# amp_soha_v4.net
KiCad netlist of a schematic drawn in EAGLE
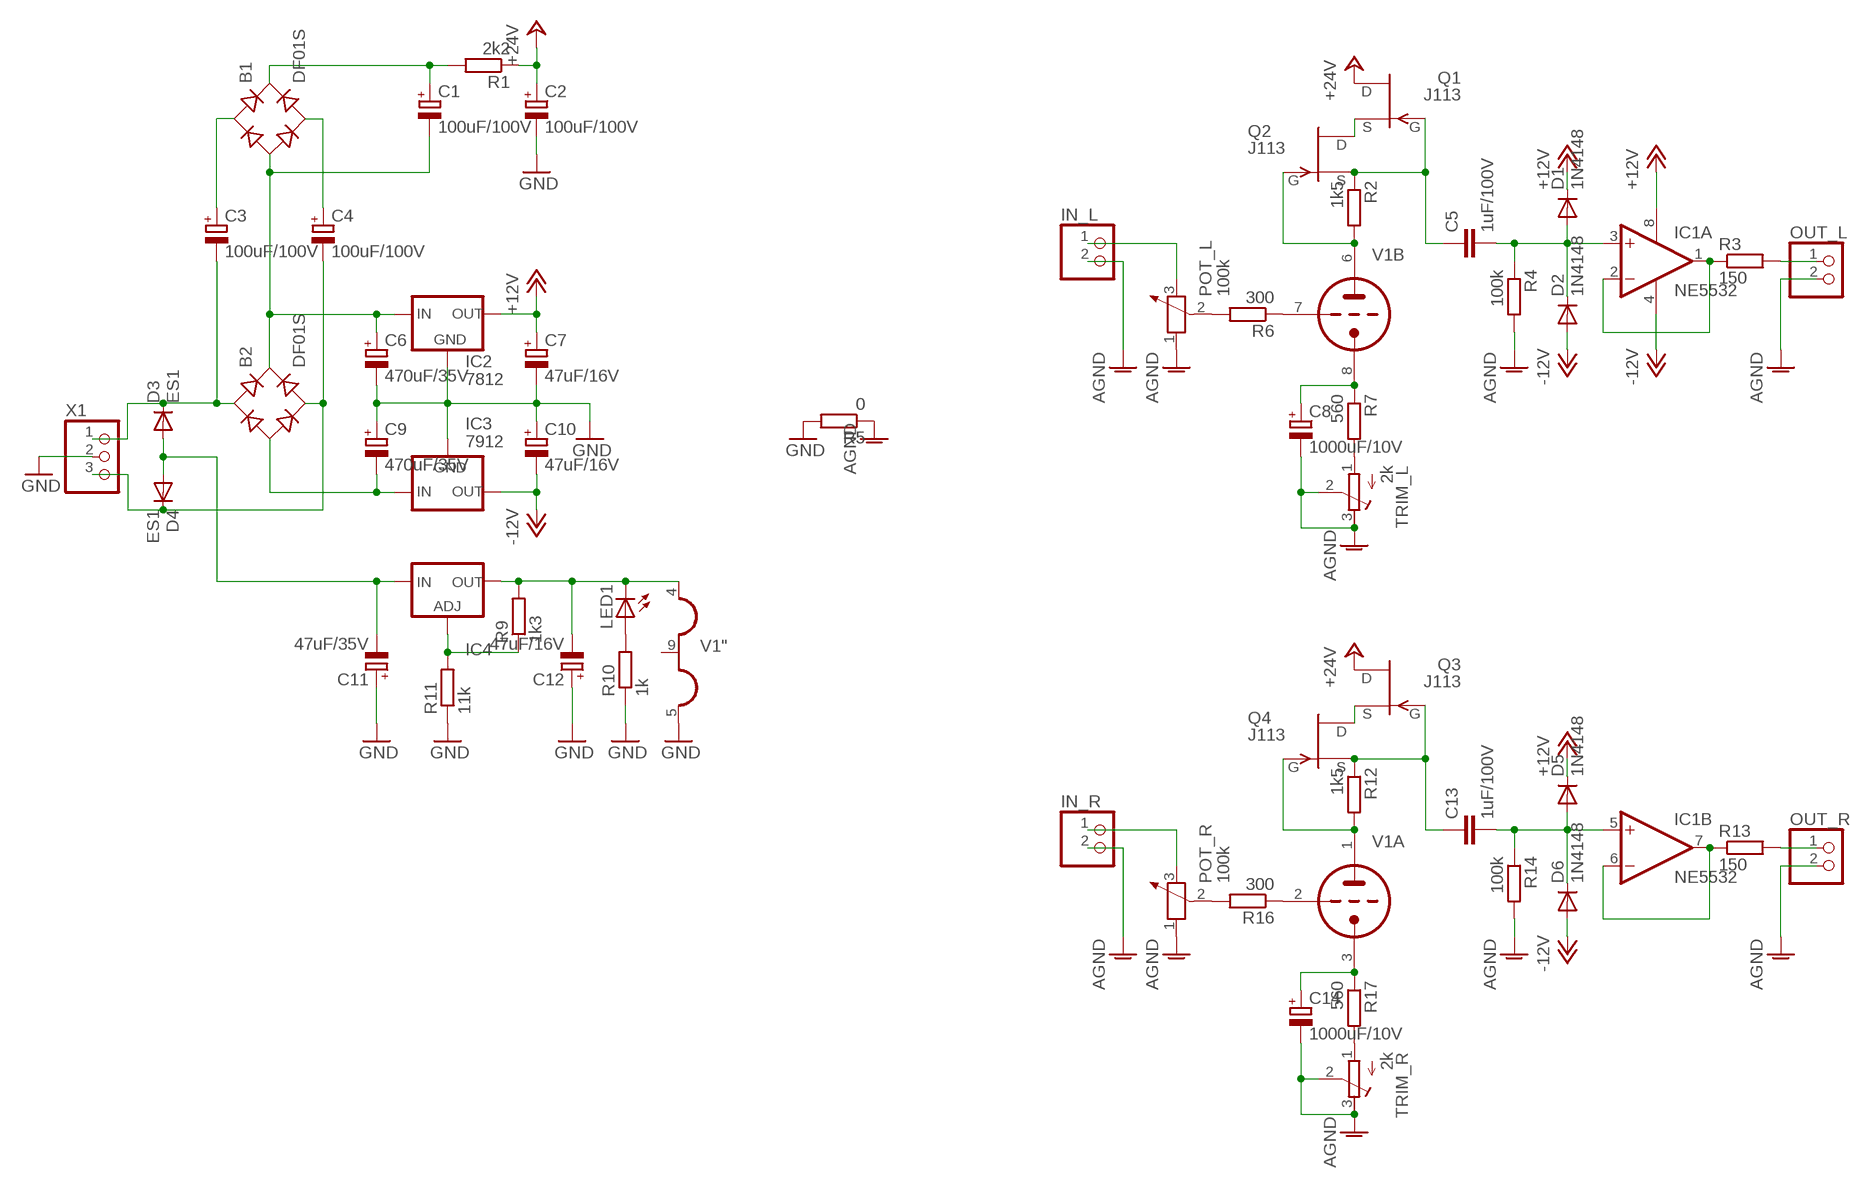
[diagram p0: schematic, sheet 1]

(export (version "E")
  (design (tool "Eeschema 10.0.6"))
  (components
    (comp (ref "B1")
      (value "DF01S")
      (footprint "eagle-import:DFS")
      (libsource (lib "eagle-import") (part "DFS01"))
    )
    (comp (ref "B2")
      (value "DF01S")
      (footprint "eagle-import:DFS")
      (libsource (lib "eagle-import") (part "DFS01"))
    )
    (comp (ref "C1")
      (value "100uF/100V")
      (footprint "eagle-import:E5-10,5")
      (libsource (lib "eagle-import") (part "CPOL-EUE5-10,5"))
    )
    (comp (ref "C2")
      (value "100uF/100V")
      (footprint "eagle-import:E5-10,5")
      (libsource (lib "eagle-import") (part "CPOL-EUE5-10,5"))
    )
    (comp (ref "C3")
      (value "100uF/100V")
      (footprint "eagle-import:E5-10,5")
      (libsource (lib "eagle-import") (part "CPOL-EUE5-10,5"))
    )
    (comp (ref "C4")
      (value "100uF/100V")
      (footprint "eagle-import:E5-10,5")
      (libsource (lib "eagle-import") (part "CPOL-EUE5-10,5"))
    )
    (comp (ref "C5")
      (value "1uF/100V")
      (footprint "eagle-import:C075-052X106")
      (libsource (lib "eagle-import") (part "C-EU075-052X106"))
    )
    (comp (ref "C6")
      (value "470uF/35V")
      (footprint "eagle-import:E5-10,5")
      (libsource (lib "eagle-import") (part "CPOL-EUE5-10,5"))
    )
    (comp (ref "C7")
      (value "47uF/16V")
      (footprint "eagle-import:E2,5-6")
      (libsource (lib "eagle-import") (part "CPOL-EUE2.5-6"))
    )
    (comp (ref "C8")
      (value "1000uF/10V")
      (footprint "eagle-import:E5-10,5")
      (libsource (lib "eagle-import") (part "CPOL-EUE5-10,5"))
    )
    (comp (ref "C9")
      (value "470uF/35V")
      (footprint "eagle-import:E5-10,5")
      (libsource (lib "eagle-import") (part "CPOL-EUE5-10,5"))
    )
    (comp (ref "C10")
      (value "47uF/16V")
      (footprint "eagle-import:E2,5-6")
      (libsource (lib "eagle-import") (part "CPOL-EUE2.5-6"))
    )
    (comp (ref "C11")
      (value "47uF/35V")
      (footprint "eagle-import:E2,5-6")
      (libsource (lib "eagle-import") (part "CPOL-EUE2.5-6"))
    )
    (comp (ref "C12")
      (value "47uF/16V")
      (footprint "eagle-import:E2,5-6")
      (libsource (lib "eagle-import") (part "CPOL-EUE2.5-6"))
    )
    (comp (ref "C13")
      (value "1uF/100V")
      (footprint "eagle-import:C075-052X106")
      (libsource (lib "eagle-import") (part "C-EU075-052X106"))
    )
    (comp (ref "C14")
      (value "1000uF/10V")
      (footprint "eagle-import:E5-10,5")
      (libsource (lib "eagle-import") (part "CPOL-EUE5-10,5"))
    )
    (comp (ref "D1")
      (value "1N4148")
      (footprint "eagle-import:D0805")
      (libsource (lib "eagle-import") (part "1N4148"))
    )
    (comp (ref "D2")
      (value "1N4148")
      (footprint "eagle-import:D0805")
      (libsource (lib "eagle-import") (part "1N4148"))
    )
    (comp (ref "D3")
      (value "ES1")
      (footprint "eagle-import:DO-214AC")
      (libsource (lib "eagle-import") (part "ES1"))
    )
    (comp (ref "D4")
      (value "ES1")
      (footprint "eagle-import:DO-214AC")
      (libsource (lib "eagle-import") (part "ES1"))
    )
    (comp (ref "D5")
      (value "1N4148")
      (footprint "eagle-import:D0805")
      (libsource (lib "eagle-import") (part "1N4148"))
    )
    (comp (ref "D6")
      (value "1N4148")
      (footprint "eagle-import:D0805")
      (libsource (lib "eagle-import") (part "1N4148"))
    )
    (comp (ref "IC1")
      (value "NE5532")
      (footprint "eagle-import:SO08")
      (libsource (lib "eagle-import") (part "NE5535U"))
    )
    (comp (ref "IC2")
      (value "7812")
      (footprint "eagle-import:78XXS")
      (libsource (lib "eagle-import") (part "78XXTO-220"))
    )
    (comp (ref "IC3")
      (value "7912")
      (footprint "eagle-import:79XXS")
      (libsource (lib "eagle-import") (part "79XXTO-220"))
    )
    (comp (ref "IC4")
      (value "LM337TS")
      (footprint "eagle-import:337TS")
      (libsource (lib "eagle-import") (part "LM337TS"))
    )
    (comp (ref "IN_L")
      (value "PINHD-1X2")
      (footprint "eagle-import:1X02")
      (libsource (lib "eagle-import") (part "PINHD-1X2"))
    )
    (comp (ref "IN_R")
      (value "PINHD-1X2")
      (footprint "eagle-import:1X02")
      (libsource (lib "eagle-import") (part "PINHD-1X2"))
    )
    (comp (ref "LED1")
      (value "LED5MM")
      (footprint "eagle-import:LED5MM")
      (libsource (lib "eagle-import") (part "LED5MM"))
    )
    (comp (ref "OUT_L")
      (value "PINHD-1X2")
      (footprint "eagle-import:1X02")
      (libsource (lib "eagle-import") (part "PINHD-1X2"))
    )
    (comp (ref "OUT_R")
      (value "PINHD-1X2")
      (footprint "eagle-import:1X02")
      (libsource (lib "eagle-import") (part "PINHD-1X2"))
    )
    (comp (ref "POT_L")
      (value "100k")
      (footprint "eagle-import:1X03")
      (libsource (lib "eagle-import") (part "POTENTIOMETER_"))
    )
    (comp (ref "POT_R")
      (value "100k")
      (footprint "eagle-import:1X03")
      (libsource (lib "eagle-import") (part "POTENTIOMETER_"))
    )
    (comp (ref "Q1")
      (value "J113")
      (footprint "eagle-import:TO92")
      (libsource (lib "eagle-import") (part "J113"))
    )
    (comp (ref "Q2")
      (value "J113")
      (footprint "eagle-import:TO92")
      (libsource (lib "eagle-import") (part "J113"))
    )
    (comp (ref "Q3")
      (value "J113")
      (footprint "eagle-import:TO92")
      (libsource (lib "eagle-import") (part "J113"))
    )
    (comp (ref "Q4")
      (value "J113")
      (footprint "eagle-import:TO92")
      (libsource (lib "eagle-import") (part "J113"))
    )
    (comp (ref "R1")
      (value "2k2")
      (footprint "eagle-import:R0805")
      (libsource (lib "eagle-import") (part "R-EU_"))
    )
    (comp (ref "R2")
      (value "1k5")
      (footprint "eagle-import:R0805")
      (libsource (lib "eagle-import") (part "R-EU_"))
    )
    (comp (ref "R3")
      (value "150")
      (footprint "eagle-import:R0805")
      (libsource (lib "eagle-import") (part "R-EU_"))
    )
    (comp (ref "R4")
      (value "100k")
      (footprint "eagle-import:R0805")
      (libsource (lib "eagle-import") (part "R-EU_"))
    )
    (comp (ref "R5")
      (value "0")
      (footprint "eagle-import:R0805")
      (libsource (lib "eagle-import") (part "R-EU_"))
    )
    (comp (ref "R6")
      (value "300")
      (footprint "eagle-import:R0805")
      (libsource (lib "eagle-import") (part "R-EU_"))
    )
    (comp (ref "R7")
      (value "560")
      (footprint "eagle-import:R0805")
      (libsource (lib "eagle-import") (part "R-EU_"))
    )
    (comp (ref "R9")
      (value "1k3")
      (footprint "eagle-import:R0805")
      (libsource (lib "eagle-import") (part "R-EU_"))
    )
    (comp (ref "R10")
      (value "1k")
      (footprint "eagle-import:R0805")
      (libsource (lib "eagle-import") (part "R-EU_"))
    )
    (comp (ref "R11")
      (value "11k")
      (footprint "eagle-import:R0805")
      (libsource (lib "eagle-import") (part "R-EU_"))
    )
    (comp (ref "R12")
      (value "1k5")
      (footprint "eagle-import:R0805")
      (libsource (lib "eagle-import") (part "R-EU_"))
    )
    (comp (ref "R13")
      (value "150")
      (footprint "eagle-import:R0805")
      (libsource (lib "eagle-import") (part "R-EU_"))
    )
    (comp (ref "R14")
      (value "100k")
      (footprint "eagle-import:R0805")
      (libsource (lib "eagle-import") (part "R-EU_"))
    )
    (comp (ref "R16")
      (value "300")
      (footprint "eagle-import:R0805")
      (libsource (lib "eagle-import") (part "R-EU_"))
    )
    (comp (ref "R17")
      (value "560")
      (footprint "eagle-import:R0805")
      (libsource (lib "eagle-import") (part "R-EU_"))
    )
    (comp (ref "TRIM_L")
      (value "2k")
      (footprint "eagle-import:RTRIM3296W")
      (libsource (lib "eagle-import") (part "RTRIM329W"))
    )
    (comp (ref "TRIM_R")
      (value "2k")
      (footprint "eagle-import:RTRIM3296W")
      (libsource (lib "eagle-import") (part "RTRIM329W"))
    )
    (comp (ref "V1")
      (value "12AU7-P")
      (footprint "eagle-import:NOVAL")
      (libsource (lib "eagle-import") (part "12AU7-P"))
    )
    (comp (ref "X1")
      (value "W237-103")
      (footprint "eagle-import:W237-103")
      (libsource (lib "eagle-import") (part "W237-103"))
    )
  )
  (nets
    (net (code "1") (name "+12V") (class "Default")
      (node (ref "C7") (pin "+") (pinfunction "+_+") (pintype "passive"))
      (node (ref "D1") (pin "K") (pinfunction "C_K") (pintype "passive"))
      (node (ref "D5") (pin "K") (pinfunction "C_K") (pintype "passive"))
      (node (ref "IC1") (pin "8") (pinfunction "V+_8") (pintype "power_in"))
      (node (ref "IC2") (pin "OUT") (pinfunction "OUT_OUT") (pintype "passive"))
    )
    (net (code "2") (name "+24V") (class "Default")
      (node (ref "C2") (pin "+") (pinfunction "+_+") (pintype "passive"))
      (node (ref "Q1") (pin "3") (pinfunction "D_3") (pintype "passive"))
      (node (ref "Q3") (pin "3") (pinfunction "D_3") (pintype "passive"))
      (node (ref "R1") (pin "1") (pinfunction "1_1") (pintype "passive"))
    )
    (net (code "3") (name "-12V") (class "Default")
      (node (ref "C10") (pin "-") (pinfunction "-_-") (pintype "passive"))
      (node (ref "D2") (pin "A") (pinfunction "A_A") (pintype "passive"))
      (node (ref "D6") (pin "A") (pinfunction "A_A") (pintype "passive"))
      (node (ref "IC1") (pin "4") (pinfunction "V-_4") (pintype "power_in"))
      (node (ref "IC3") (pin "OUT") (pinfunction "OUT_OUT") (pintype "passive"))
    )
    (net (code "4") (name "AGND") (class "Default")
      (node (ref "C14") (pin "-") (pinfunction "-_-") (pintype "passive"))
      (node (ref "C8") (pin "-") (pinfunction "-_-") (pintype "passive"))
      (node (ref "IN_L") (pin "2") (pinfunction "2_2") (pintype "passive"))
      (node (ref "IN_R") (pin "2") (pinfunction "2_2") (pintype "passive"))
      (node (ref "OUT_L") (pin "2") (pinfunction "2_2") (pintype "passive"))
      (node (ref "OUT_R") (pin "2") (pinfunction "2_2") (pintype "passive"))
      (node (ref "POT_L") (pin "1") (pinfunction "1_1") (pintype "passive"))
      (node (ref "POT_R") (pin "1") (pinfunction "1_1") (pintype "passive"))
      (node (ref "R14") (pin "2") (pinfunction "2_2") (pintype "passive"))
      (node (ref "R4") (pin "2") (pinfunction "2_2") (pintype "passive"))
      (node (ref "R5") (pin "1") (pinfunction "1_1") (pintype "passive"))
      (node (ref "TRIM_L") (pin "2") (pinfunction "S_2") (pintype "passive"))
      (node (ref "TRIM_L") (pin "3") (pinfunction "E_3") (pintype "passive"))
      (node (ref "TRIM_R") (pin "2") (pinfunction "S_2") (pintype "passive"))
      (node (ref "TRIM_R") (pin "3") (pinfunction "E_3") (pintype "passive"))
    )
    (net (code "5") (name "GND") (class "Default")
      (node (ref "C10") (pin "+") (pinfunction "+_+") (pintype "passive"))
      (node (ref "C11") (pin "+") (pinfunction "+_+") (pintype "passive"))
      (node (ref "C12") (pin "+") (pinfunction "+_+") (pintype "passive"))
      (node (ref "C2") (pin "-") (pinfunction "-_-") (pintype "passive"))
      (node (ref "C6") (pin "-") (pinfunction "-_-") (pintype "passive"))
      (node (ref "C7") (pin "-") (pinfunction "-_-") (pintype "passive"))
      (node (ref "C9") (pin "+") (pinfunction "+_+") (pintype "passive"))
      (node (ref "IC2") (pin "GND") (pinfunction "GND_GND") (pintype "input"))
      (node (ref "IC3") (pin "GND") (pinfunction "GND_GND") (pintype "input"))
      (node (ref "R10") (pin "1") (pinfunction "1_1") (pintype "passive"))
      (node (ref "R11") (pin "1") (pinfunction "1_1") (pintype "passive"))
      (node (ref "R5") (pin "2") (pinfunction "2_2") (pintype "passive"))
      (node (ref "V1") (pin "5") (pinfunction "H3_5") (pintype "passive"))
      (node (ref "X1") (pin "2") (pinfunction "2_2") (pintype "passive"))
    )
    (net (code "6") (name "Net-(B1-Pad+)") (class "Default")
      (node (ref "B1") (pin "+") (pinfunction "+_+") (pintype "passive"))
      (node (ref "C1") (pin "+") (pinfunction "+_+") (pintype "passive"))
      (node (ref "R1") (pin "2") (pinfunction "2_2") (pintype "passive"))
    )
    (net (code "7") (name "Net-(B1-Pad-)") (class "Default")
      (node (ref "B1") (pin "-") (pinfunction "-_-") (pintype "passive"))
      (node (ref "B2") (pin "+") (pinfunction "+_+") (pintype "passive"))
      (node (ref "C1") (pin "-") (pinfunction "-_-") (pintype "passive"))
      (node (ref "C6") (pin "+") (pinfunction "+_+") (pintype "passive"))
      (node (ref "IC2") (pin "IN") (pinfunction "IN_IN") (pintype "input"))
    )
    (net (code "8") (name "Net-(B1-PadAC1)") (class "Default")
      (node (ref "B1") (pin "AC1") (pinfunction "AC1_AC1") (pintype "passive"))
      (node (ref "C3") (pin "+") (pinfunction "+_+") (pintype "passive"))
    )
    (net (code "9") (name "Net-(B1-PadAC2)") (class "Default")
      (node (ref "B1") (pin "AC2") (pinfunction "AC2_AC2") (pintype "passive"))
      (node (ref "C4") (pin "+") (pinfunction "+_+") (pintype "passive"))
    )
    (net (code "10") (name "Net-(B2-Pad-)") (class "Default")
      (node (ref "B2") (pin "-") (pinfunction "-_-") (pintype "passive"))
      (node (ref "C9") (pin "-") (pinfunction "-_-") (pintype "passive"))
      (node (ref "IC3") (pin "IN") (pinfunction "IN_IN") (pintype "input"))
    )
    (net (code "11") (name "Net-(B2-PadAC1)") (class "Default")
      (node (ref "B2") (pin "AC1") (pinfunction "AC1_AC1") (pintype "passive"))
      (node (ref "C3") (pin "-") (pinfunction "-_-") (pintype "passive"))
      (node (ref "D3") (pin "C") (pinfunction "C_C") (pintype "passive"))
      (node (ref "X1") (pin "1") (pinfunction "1_1") (pintype "passive"))
    )
    (net (code "12") (name "Net-(B2-PadAC2)") (class "Default")
      (node (ref "B2") (pin "AC2") (pinfunction "AC2_AC2") (pintype "passive"))
      (node (ref "C4") (pin "-") (pinfunction "-_-") (pintype "passive"))
      (node (ref "D4") (pin "C") (pinfunction "C_C") (pintype "passive"))
      (node (ref "X1") (pin "3") (pinfunction "3_3") (pintype "passive"))
    )
    (net (code "13") (name "Net-(D2-C)") (class "Default")
      (node (ref "C5") (pin "2") (pinfunction "2_2") (pintype "passive"))
      (node (ref "D1") (pin "A") (pinfunction "A_A") (pintype "passive"))
      (node (ref "D2") (pin "K") (pinfunction "C_K") (pintype "passive"))
      (node (ref "IC1") (pin "3") (pinfunction "+IN_3") (pintype "input"))
      (node (ref "R4") (pin "1") (pinfunction "1_1") (pintype "passive"))
    )
    (net (code "14") (name "Net-(D6-C)") (class "Default")
      (node (ref "C13") (pin "2") (pinfunction "2_2") (pintype "passive"))
      (node (ref "D5") (pin "A") (pinfunction "A_A") (pintype "passive"))
      (node (ref "D6") (pin "K") (pinfunction "C_K") (pintype "passive"))
      (node (ref "IC1") (pin "5") (pinfunction "+IN_5") (pintype "input"))
      (node (ref "R14") (pin "1") (pinfunction "1_1") (pintype "passive"))
    )
    (net (code "15") (name "Net-(IC1A--IN)") (class "Default")
      (node (ref "IC1") (pin "1") (pinfunction "OUT_1") (pintype "output"))
      (node (ref "IC1") (pin "2") (pinfunction "-IN_2") (pintype "input"))
      (node (ref "R3") (pin "1") (pinfunction "1_1") (pintype "passive"))
    )
    (net (code "16") (name "Net-(IC1B--IN)") (class "Default")
      (node (ref "IC1") (pin "6") (pinfunction "-IN_6") (pintype "input"))
      (node (ref "IC1") (pin "7") (pinfunction "OUT_7") (pintype "output"))
      (node (ref "R13") (pin "1") (pinfunction "1_1") (pintype "passive"))
    )
    (net (code "17") (name "Net-(IC4-ADJ)") (class "Default")
      (node (ref "IC4") (pin "1") (pinfunction "ADJ_1") (pintype "input"))
      (node (ref "R11") (pin "2") (pinfunction "2_2") (pintype "passive"))
      (node (ref "R9") (pin "1") (pinfunction "1_1") (pintype "passive"))
    )
    (net (code "18") (name "Net-(IC4-IN)") (class "Default")
      (node (ref "C11") (pin "-") (pinfunction "-_-") (pintype "passive"))
      (node (ref "D3") (pin "A") (pinfunction "A_A") (pintype "passive"))
      (node (ref "D4") (pin "A") (pinfunction "A_A") (pintype "passive"))
      (node (ref "IC4") (pin "2") (pinfunction "IN_2") (pintype "input"))
    )
    (net (code "19") (name "Net-(IC4-OUT)") (class "Default")
      (node (ref "C12") (pin "-") (pinfunction "-_-") (pintype "passive"))
      (node (ref "IC4") (pin "3") (pinfunction "OUT_3") (pintype "passive"))
      (node (ref "LED1") (pin "K") (pinfunction "C_K") (pintype "passive"))
      (node (ref "R9") (pin "2") (pinfunction "2_2") (pintype "passive"))
      (node (ref "V1") (pin "4") (pinfunction "H1_4") (pintype "passive"))
    )
    (net (code "20") (name "Net-(LED1-PadA)") (class "Default")
      (node (ref "LED1") (pin "A") (pinfunction "A_A") (pintype "passive"))
      (node (ref "R10") (pin "2") (pinfunction "2_2") (pintype "passive"))
    )
    (net (code "21") (name "Net-(OUT_L-Pad1)") (class "Default")
      (node (ref "OUT_L") (pin "1") (pinfunction "1_1") (pintype "passive"))
      (node (ref "R3") (pin "2") (pinfunction "2_2") (pintype "passive"))
    )
    (net (code "22") (name "Net-(OUT_R-Pad1)") (class "Default")
      (node (ref "OUT_R") (pin "1") (pinfunction "1_1") (pintype "passive"))
      (node (ref "R13") (pin "2") (pinfunction "2_2") (pintype "passive"))
    )
    (net (code "23") (name "Net-(POT_L-2)") (class "Default")
      (node (ref "IN_L") (pin "1") (pinfunction "1_1") (pintype "passive"))
      (node (ref "POT_L") (pin "3") (pinfunction "2_3") (pintype "passive"))
    )
    (net (code "24") (name "Net-(POT_L-3)") (class "Default")
      (node (ref "POT_L") (pin "2") (pinfunction "3_2") (pintype "passive"))
      (node (ref "R6") (pin "2") (pinfunction "2_2") (pintype "passive"))
    )
    (net (code "25") (name "Net-(POT_R-2)") (class "Default")
      (node (ref "IN_R") (pin "1") (pinfunction "1_1") (pintype "passive"))
      (node (ref "POT_R") (pin "3") (pinfunction "2_3") (pintype "passive"))
    )
    (net (code "26") (name "Net-(POT_R-3)") (class "Default")
      (node (ref "POT_R") (pin "2") (pinfunction "3_2") (pintype "passive"))
      (node (ref "R16") (pin "2") (pinfunction "2_2") (pintype "passive"))
    )
    (net (code "27") (name "Net-(Q1-G)") (class "Default")
      (node (ref "C5") (pin "1") (pinfunction "1_1") (pintype "passive"))
      (node (ref "Q1") (pin "1") (pinfunction "G_1") (pintype "passive"))
      (node (ref "Q2") (pin "2") (pinfunction "S_2") (pintype "passive"))
      (node (ref "R2") (pin "1") (pinfunction "1_1") (pintype "passive"))
    )
    (net (code "28") (name "Net-(Q1-S)") (class "Default")
      (node (ref "Q1") (pin "2") (pinfunction "S_2") (pintype "passive"))
      (node (ref "Q2") (pin "3") (pinfunction "D_3") (pintype "passive"))
    )
    (net (code "29") (name "Net-(Q2-G)") (class "Default")
      (node (ref "Q2") (pin "1") (pinfunction "G_1") (pintype "passive"))
      (node (ref "R2") (pin "2") (pinfunction "2_2") (pintype "passive"))
      (node (ref "V1") (pin "6") (pinfunction "TA_6") (pintype "passive"))
    )
    (net (code "30") (name "Net-(Q3-G)") (class "Default")
      (node (ref "C13") (pin "1") (pinfunction "1_1") (pintype "passive"))
      (node (ref "Q3") (pin "1") (pinfunction "G_1") (pintype "passive"))
      (node (ref "Q4") (pin "2") (pinfunction "S_2") (pintype "passive"))
      (node (ref "R12") (pin "1") (pinfunction "1_1") (pintype "passive"))
    )
    (net (code "31") (name "Net-(Q3-S)") (class "Default")
      (node (ref "Q3") (pin "2") (pinfunction "S_2") (pintype "passive"))
      (node (ref "Q4") (pin "3") (pinfunction "D_3") (pintype "passive"))
    )
    (net (code "32") (name "Net-(Q4-G)") (class "Default")
      (node (ref "Q4") (pin "1") (pinfunction "G_1") (pintype "passive"))
      (node (ref "R12") (pin "2") (pinfunction "2_2") (pintype "passive"))
      (node (ref "V1") (pin "1") (pinfunction "TA_1") (pintype "passive"))
    )
    (net (code "33") (name "Net-(TRIM_L-A)") (class "Default")
      (node (ref "R7") (pin "2") (pinfunction "2_2") (pintype "passive"))
      (node (ref "TRIM_L") (pin "1") (pinfunction "A_1") (pintype "passive"))
    )
    (net (code "34") (name "Net-(TRIM_R-A)") (class "Default")
      (node (ref "R17") (pin "2") (pinfunction "2_2") (pintype "passive"))
      (node (ref "TRIM_R") (pin "1") (pinfunction "A_1") (pintype "passive"))
    )
    (net (code "35") (name "Net-(V1B-TG)") (class "Default")
      (node (ref "R16") (pin "1") (pinfunction "1_1") (pintype "passive"))
      (node (ref "V1") (pin "2") (pinfunction "TG_2") (pintype "passive"))
    )
    (net (code "36") (name "Net-(V1B-TK)") (class "Default")
      (node (ref "C14") (pin "+") (pinfunction "+_+") (pintype "passive"))
      (node (ref "R17") (pin "1") (pinfunction "1_1") (pintype "passive"))
      (node (ref "V1") (pin "3") (pinfunction "TK_3") (pintype "passive"))
    )
    (net (code "37") (name "Net-(V1C-TG)") (class "Default")
      (node (ref "R6") (pin "1") (pinfunction "1_1") (pintype "passive"))
      (node (ref "V1") (pin "7") (pinfunction "TG_7") (pintype "passive"))
    )
    (net (code "38") (name "Net-(V1C-TK)") (class "Default")
      (node (ref "C8") (pin "+") (pinfunction "+_+") (pintype "passive"))
      (node (ref "R7") (pin "1") (pinfunction "1_1") (pintype "passive"))
      (node (ref "V1") (pin "8") (pinfunction "TK_8") (pintype "passive"))
    )
    (net (code "39") (name "unconnected-(V1A-H2-Pad9)") (class "Default")
      (node (ref "V1") (pin "9") (pinfunction "H2_9") (pintype "passive"))
    )
  )
)
